# schematic.net
KiCad netlist of a schematic drawn in EasyEDA
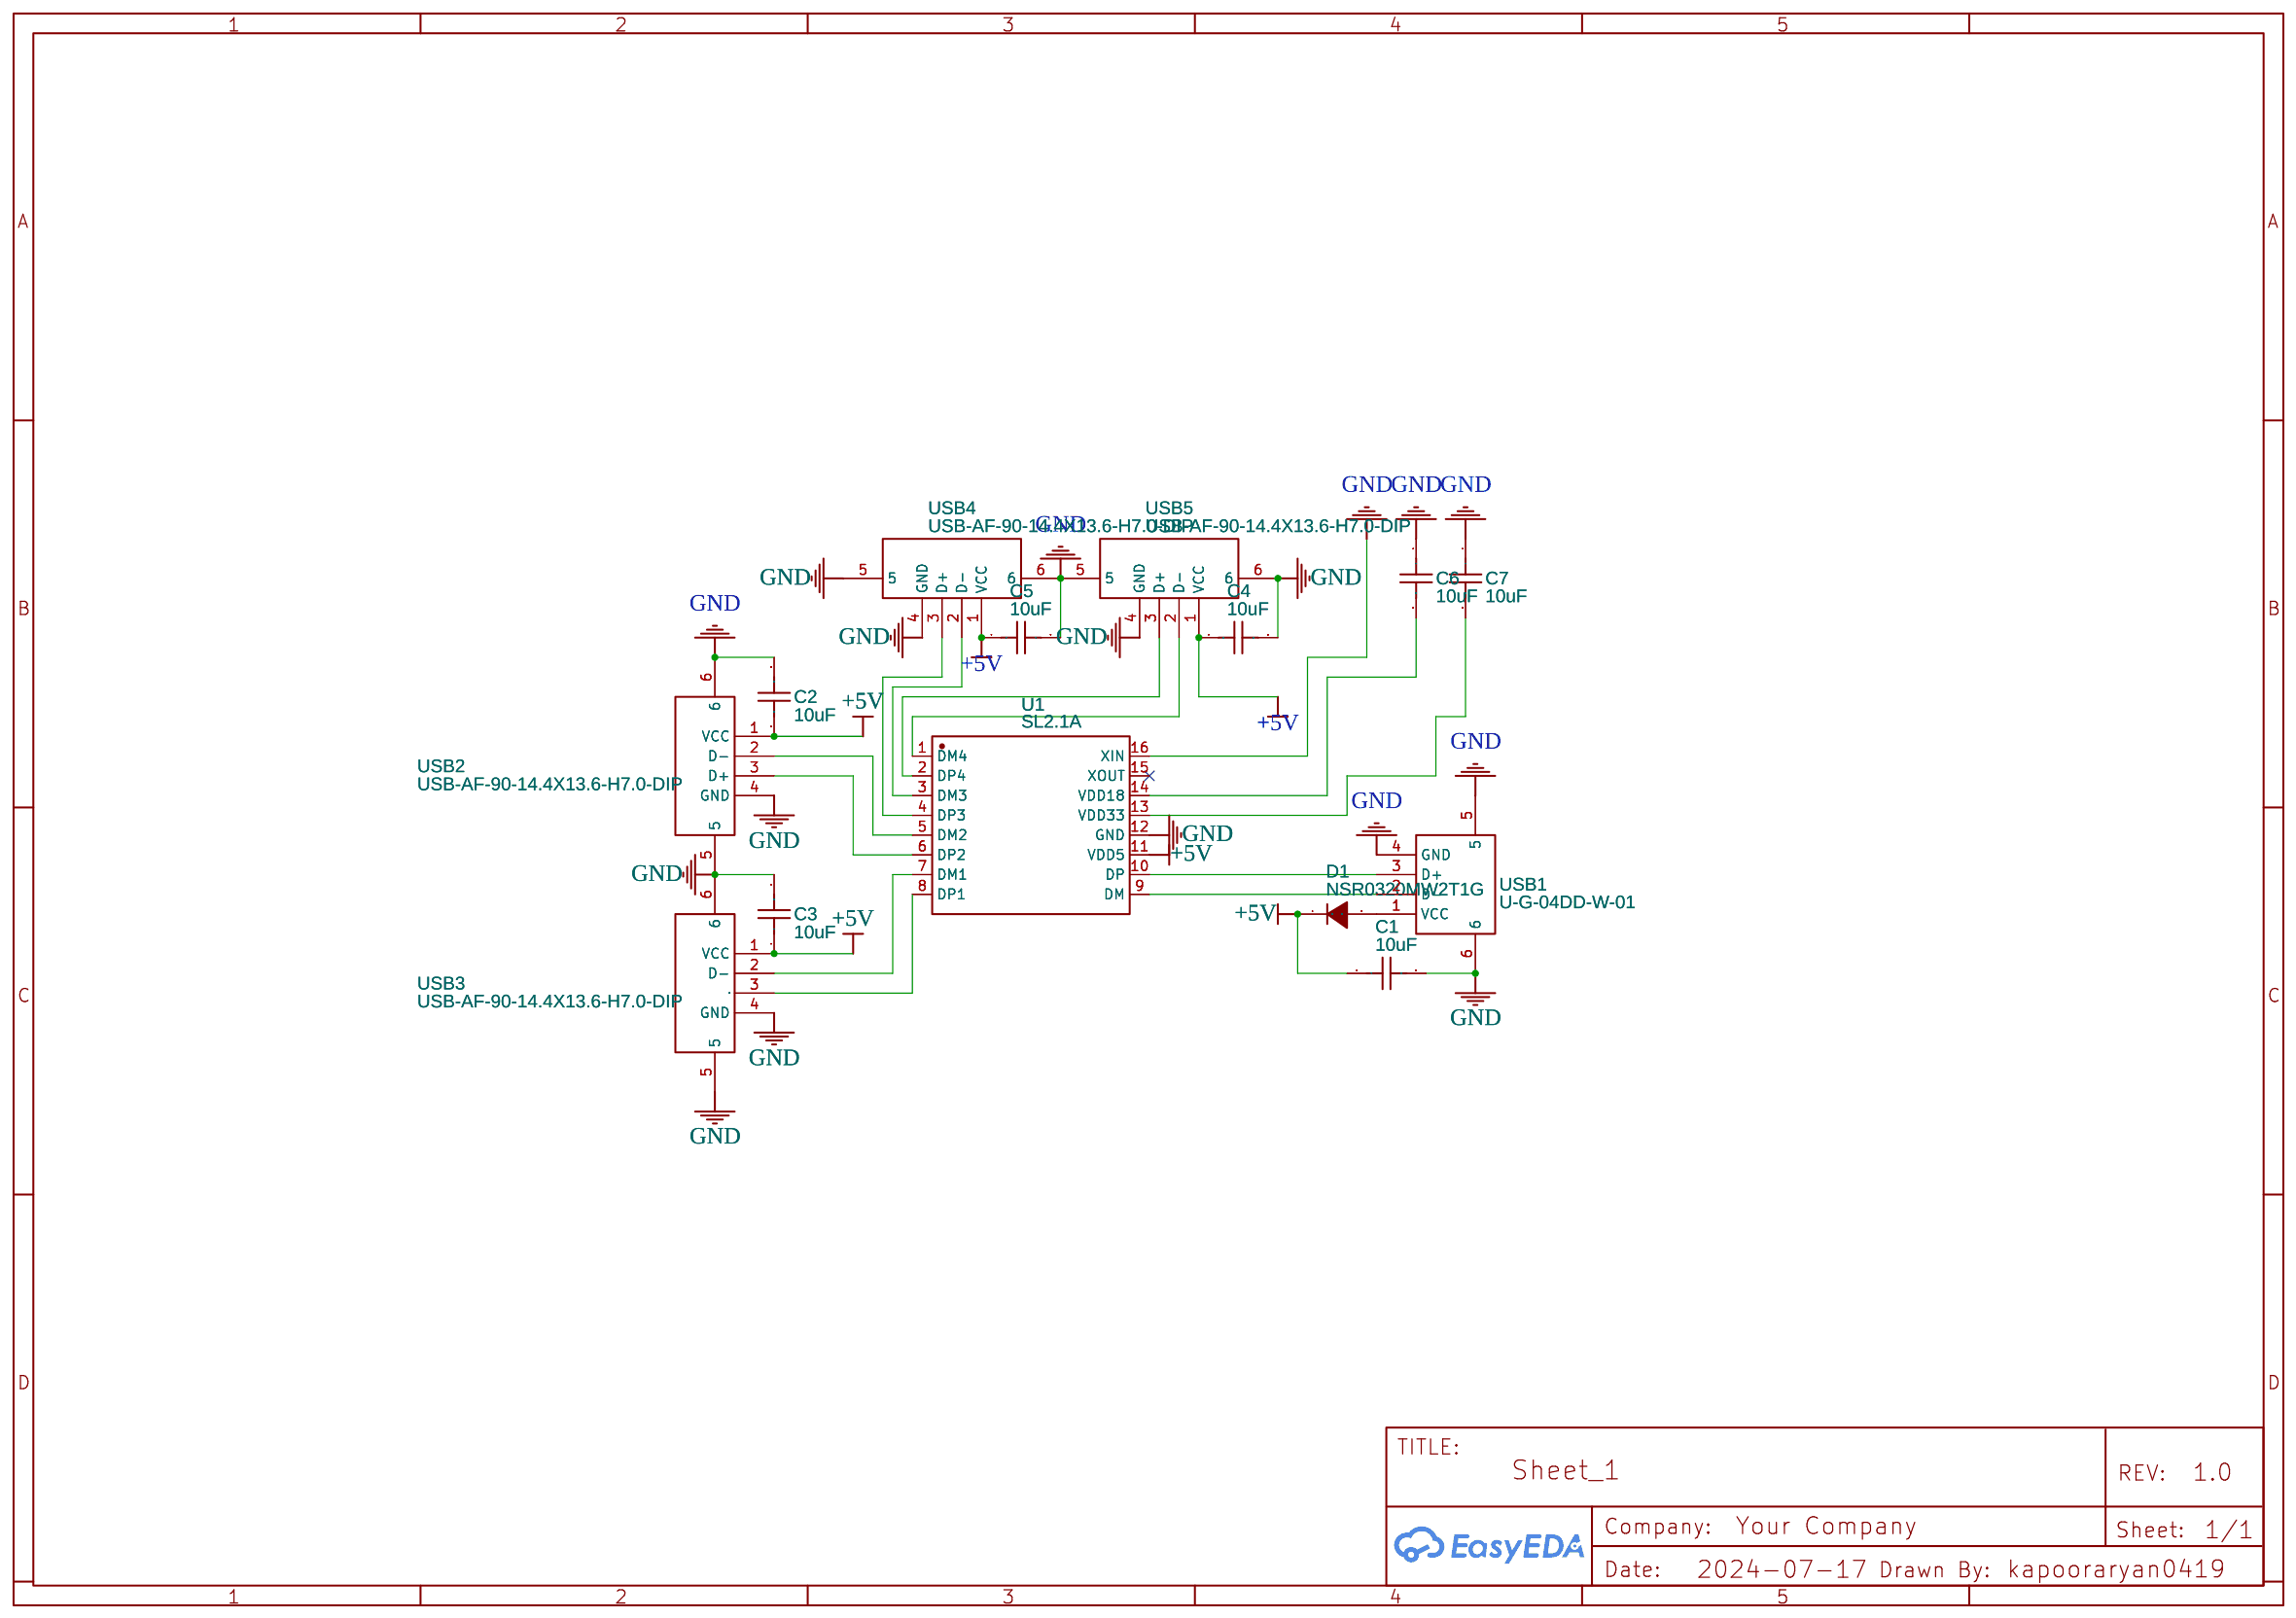
[diagram p0: schematic sheet]

(export (version "E")
  (design (tool "Eeschema 10.0.6"))
  (components
    (comp (ref "C1")
      (value "10uF")
      (fields
        (field (name "Manufacturer Part") "CL10A106KP8NNNC")
        (field (name "Manufacturer") "SAMSUNG(三星)")
      )
      (libsource (lib "") (part "CL10A106KP8NNNC"))
    )
    (comp (ref "C2")
      (value "10uF")
      (fields
        (field (name "Manufacturer Part") "CL10A106KP8NNNC")
        (field (name "Manufacturer") "SAMSUNG(三星)")
      )
      (libsource (lib "") (part "CL10A106KP8NNNC_2"))
    )
    (comp (ref "C3")
      (value "10uF")
      (fields
        (field (name "Manufacturer Part") "CL10A106KP8NNNC")
        (field (name "Manufacturer") "SAMSUNG(三星)")
      )
      (libsource (lib "") (part "CL10A106KP8NNNC_2"))
    )
    (comp (ref "C4")
      (value "10uF")
      (fields
        (field (name "Manufacturer Part") "CL10A106KP8NNNC")
        (field (name "Manufacturer") "SAMSUNG(三星)")
      )
      (libsource (lib "") (part "CL10A106KP8NNNC"))
    )
    (comp (ref "C5")
      (value "10uF")
      (fields
        (field (name "Manufacturer Part") "CL10A106KP8NNNC")
        (field (name "Manufacturer") "SAMSUNG(三星)")
      )
      (libsource (lib "") (part "CL10A106KP8NNNC"))
    )
    (comp (ref "C6")
      (value "10uF")
      (fields
        (field (name "Manufacturer Part") "CL10A106KP8NNNC")
        (field (name "Manufacturer") "SAMSUNG(三星)")
      )
      (libsource (lib "") (part "CL10A106KP8NNNC_1"))
    )
    (comp (ref "C7")
      (value "10uF")
      (fields
        (field (name "Manufacturer Part") "CL10A106KP8NNNC")
        (field (name "Manufacturer") "SAMSUNG(三星)")
      )
      (libsource (lib "") (part "CL10A106KP8NNNC_1"))
    )
    (comp (ref "D1")
      (value "NSR0320MW2T1G")
      (fields (field (name "Manufacturer") "onsemi(安森美)"))
      (libsource (lib "") (part "NSR0320MW2T1G"))
    )
    (comp (ref "U1")
      (value "SL2.1A")
      (fields (field (name "Manufacturer") "CoreChips(和芯润德)"))
      (libsource (lib "") (part "SL2.1A"))
    )
    (comp (ref "USB1")
      (value "U-G-04DD-W-01")
      (fields (field (name "Manufacturer Part") "U-G-O4DD-W-1") (field (name "Manufacturer") "韩国韩荣"))
      (libsource (lib "") (part "U-G-04DD-W-01"))
    )
    (comp (ref "USB2")
      (value "USB-AF-90-14.4X13.6-H7.0-DIP")
      (fields (field (name "Manufacturer Part") "903-131A1011D10100") (field (name "Manufacturer") "精拓金"))
      (libsource (lib "") (part "USB-AF-90-14.4X13.6-H7.0-DIP_1"))
    )
    (comp (ref "USB3")
      (value "USB-AF-90-14.4X13.6-H7.0-DIP")
      (fields (field (name "Manufacturer Part") "903-131A1011D10100") (field (name "Manufacturer") "精拓金"))
      (libsource (lib "") (part "USB-AF-90-14.4X13.6-H7.0-DIP_1"))
    )
    (comp (ref "USB4")
      (value "USB-AF-90-14.4X13.6-H7.0-DIP")
      (fields (field (name "Manufacturer Part") "903-131A1011D10100") (field (name "Manufacturer") "精拓金"))
      (libsource (lib "") (part "USB-AF-90-14.4X13.6-H7.0-DIP"))
    )
    (comp (ref "USB5")
      (value "USB-AF-90-14.4X13.6-H7.0-DIP")
      (fields (field (name "Manufacturer Part") "903-131A1011D10100") (field (name "Manufacturer") "精拓金"))
      (libsource (lib "") (part "USB-AF-90-14.4X13.6-H7.0-DIP"))
    )
  )
  (nets
    (net (code "1") (name "+5V") (class "Default")
      (node (ref "C1") (pin "1") (pinfunction "1_1") (pintype "unspecified"))
      (node (ref "C2") (pin "1") (pinfunction "1_1") (pintype "unspecified"))
      (node (ref "C3") (pin "1") (pinfunction "1_1") (pintype "unspecified"))
      (node (ref "C4") (pin "1") (pinfunction "1_1") (pintype "unspecified"))
      (node (ref "C5") (pin "1") (pinfunction "1_1") (pintype "unspecified"))
      (node (ref "D1") (pin "1") (pinfunction "C_1") (pintype "unspecified"))
      (node (ref "U1") (pin "11") (pinfunction "VDD5_11") (pintype "unspecified"))
      (node (ref "USB2") (pin "1") (pinfunction "VCC_1") (pintype "unspecified"))
      (node (ref "USB3") (pin "1") (pinfunction "VCC_1") (pintype "unspecified"))
      (node (ref "USB4") (pin "1") (pinfunction "VCC_1") (pintype "unspecified"))
      (node (ref "USB5") (pin "1") (pinfunction "VCC_1") (pintype "unspecified"))
    )
    (net (code "2") (name "GND") (class "Default")
      (node (ref "C1") (pin "2") (pinfunction "2_2") (pintype "unspecified"))
      (node (ref "C2") (pin "2") (pinfunction "2_2") (pintype "unspecified"))
      (node (ref "C3") (pin "2") (pinfunction "2_2") (pintype "unspecified"))
      (node (ref "C4") (pin "2") (pinfunction "2_2") (pintype "unspecified"))
      (node (ref "C5") (pin "2") (pinfunction "2_2") (pintype "unspecified"))
      (node (ref "C6") (pin "1") (pinfunction "1_1") (pintype "unspecified"))
      (node (ref "C7") (pin "1") (pinfunction "1_1") (pintype "unspecified"))
      (node (ref "U1") (pin "12") (pinfunction "GND_12") (pintype "unspecified"))
      (node (ref "U1") (pin "16") (pinfunction "XIN_16") (pintype "unspecified"))
      (node (ref "USB1") (pin "4") (pinfunction "GND_4") (pintype "unspecified"))
      (node (ref "USB1") (pin "5") (pinfunction "5_5") (pintype "unspecified"))
      (node (ref "USB1") (pin "6") (pinfunction "6_6") (pintype "unspecified"))
      (node (ref "USB2") (pin "4") (pinfunction "GND_4") (pintype "unspecified"))
      (node (ref "USB2") (pin "5") (pinfunction "5_5") (pintype "unspecified"))
      (node (ref "USB2") (pin "6") (pinfunction "6_6") (pintype "unspecified"))
      (node (ref "USB3") (pin "4") (pinfunction "GND_4") (pintype "unspecified"))
      (node (ref "USB3") (pin "5") (pinfunction "5_5") (pintype "unspecified"))
      (node (ref "USB3") (pin "6") (pinfunction "6_6") (pintype "unspecified"))
      (node (ref "USB4") (pin "4") (pinfunction "GND_4") (pintype "unspecified"))
      (node (ref "USB4") (pin "5") (pinfunction "5_5") (pintype "unspecified"))
      (node (ref "USB4") (pin "6") (pinfunction "6_6") (pintype "unspecified"))
      (node (ref "USB5") (pin "4") (pinfunction "GND_4") (pintype "unspecified"))
      (node (ref "USB5") (pin "5") (pinfunction "5_5") (pintype "unspecified"))
      (node (ref "USB5") (pin "6") (pinfunction "6_6") (pintype "unspecified"))
    )
    (net (code "3") (name "Net-(D1-A)") (class "Default")
      (node (ref "D1") (pin "2") (pinfunction "A_2") (pintype "unspecified"))
      (node (ref "USB1") (pin "1") (pinfunction "VCC_1") (pintype "unspecified"))
    )
    (net (code "4") (name "Net-(U1-DM)") (class "Default")
      (node (ref "U1") (pin "9") (pinfunction "DM_9") (pintype "unspecified"))
      (node (ref "USB1") (pin "2") (pinfunction "D-_2") (pintype "unspecified"))
    )
    (net (code "5") (name "Net-(U1-DM1)") (class "Default")
      (node (ref "U1") (pin "7") (pinfunction "DM1_7") (pintype "unspecified"))
      (node (ref "USB3") (pin "2") (pinfunction "D-_2") (pintype "unspecified"))
    )
    (net (code "6") (name "Net-(U1-DM2)") (class "Default")
      (node (ref "U1") (pin "5") (pinfunction "DM2_5") (pintype "unspecified"))
      (node (ref "USB2") (pin "2") (pinfunction "D-_2") (pintype "unspecified"))
    )
    (net (code "7") (name "Net-(U1-DM3)") (class "Default")
      (node (ref "U1") (pin "3") (pinfunction "DM3_3") (pintype "unspecified"))
      (node (ref "USB4") (pin "2") (pinfunction "D-_2") (pintype "unspecified"))
    )
    (net (code "8") (name "Net-(U1-DM4)") (class "Default")
      (node (ref "U1") (pin "1") (pinfunction "DM4_1") (pintype "unspecified"))
      (node (ref "USB5") (pin "2") (pinfunction "D-_2") (pintype "unspecified"))
    )
    (net (code "9") (name "Net-(U1-DP)") (class "Default")
      (node (ref "U1") (pin "10") (pinfunction "DP_10") (pintype "unspecified"))
      (node (ref "USB1") (pin "3") (pinfunction "D+_3") (pintype "unspecified"))
    )
    (net (code "10") (name "Net-(U1-DP1)") (class "Default")
      (node (ref "U1") (pin "8") (pinfunction "DP1_8") (pintype "unspecified"))
      (node (ref "USB3") (pin "3") (pinfunction "D+_3") (pintype "unspecified"))
    )
    (net (code "11") (name "Net-(U1-DP2)") (class "Default")
      (node (ref "U1") (pin "6") (pinfunction "DP2_6") (pintype "unspecified"))
      (node (ref "USB2") (pin "3") (pinfunction "D+_3") (pintype "unspecified"))
    )
    (net (code "12") (name "Net-(U1-DP3)") (class "Default")
      (node (ref "U1") (pin "4") (pinfunction "DP3_4") (pintype "unspecified"))
      (node (ref "USB4") (pin "3") (pinfunction "D+_3") (pintype "unspecified"))
    )
    (net (code "13") (name "Net-(U1-DP4)") (class "Default")
      (node (ref "U1") (pin "2") (pinfunction "DP4_2") (pintype "unspecified"))
      (node (ref "USB5") (pin "3") (pinfunction "D+_3") (pintype "unspecified"))
    )
    (net (code "14") (name "Net-(U1-VDD18)") (class "Default")
      (node (ref "C6") (pin "2") (pinfunction "2_2") (pintype "unspecified"))
      (node (ref "U1") (pin "14") (pinfunction "VDD18_14") (pintype "unspecified"))
    )
    (net (code "15") (name "Net-(U1-VDD33)") (class "Default")
      (node (ref "C7") (pin "2") (pinfunction "2_2") (pintype "unspecified"))
      (node (ref "U1") (pin "13") (pinfunction "VDD33_13") (pintype "unspecified"))
    )
    (net (code "16") (name "unconnected-(U1-XOUT-Pad15)") (class "Default")
      (node (ref "U1") (pin "15") (pinfunction "XOUT_15") (pintype "unspecified+no_connect"))
    )
  )
)
